# motherboard.net
KiCad netlist of a schematic drawn in EAGLE
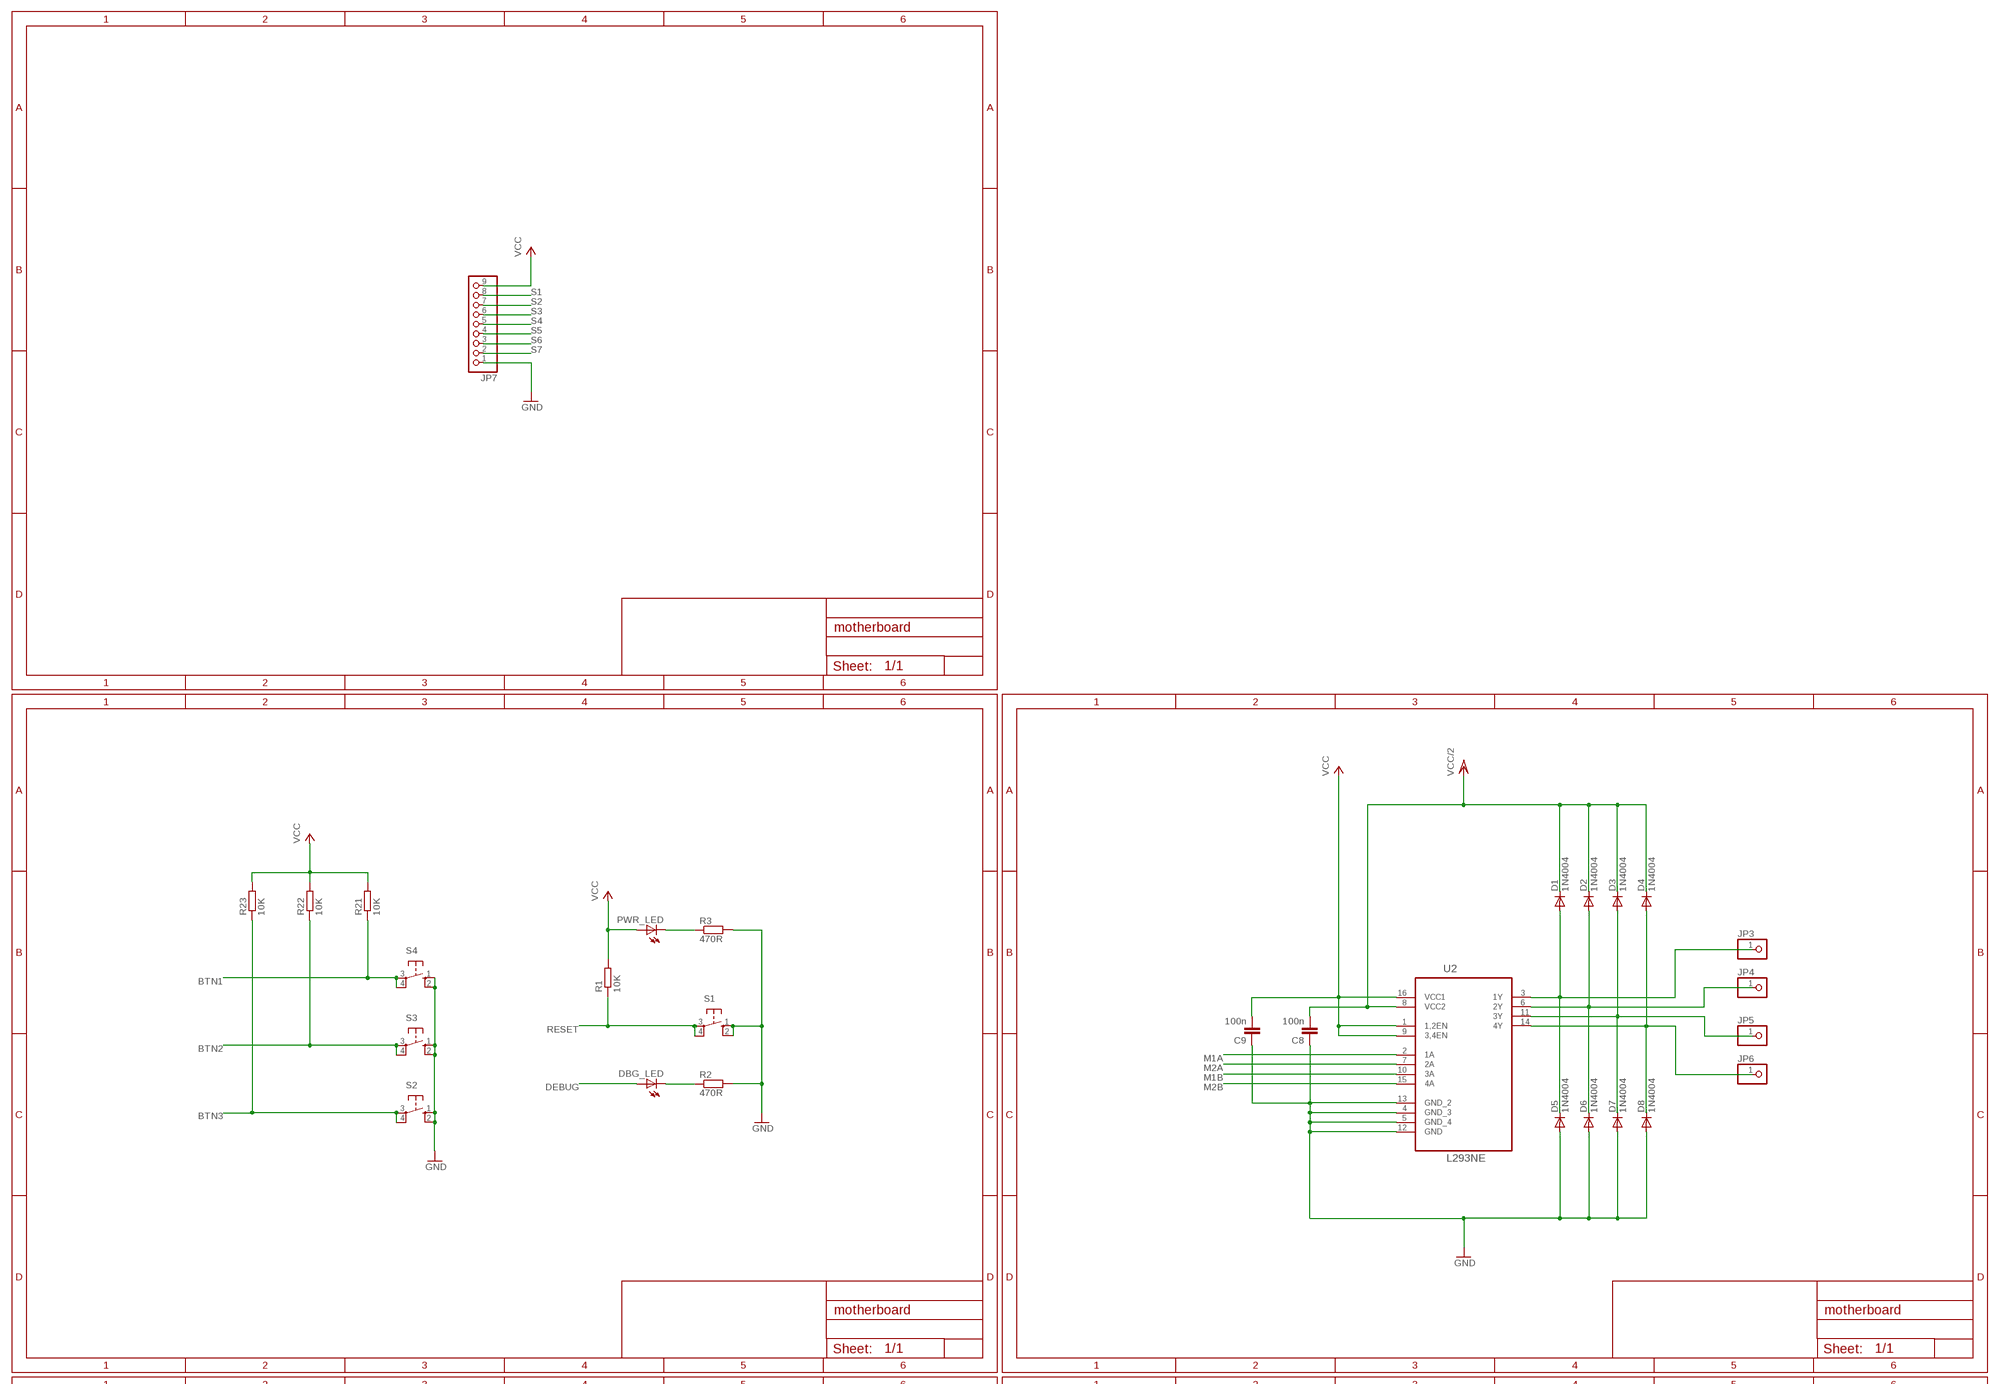
[diagram p0: schematic, sheet 1, part 1 of 2]
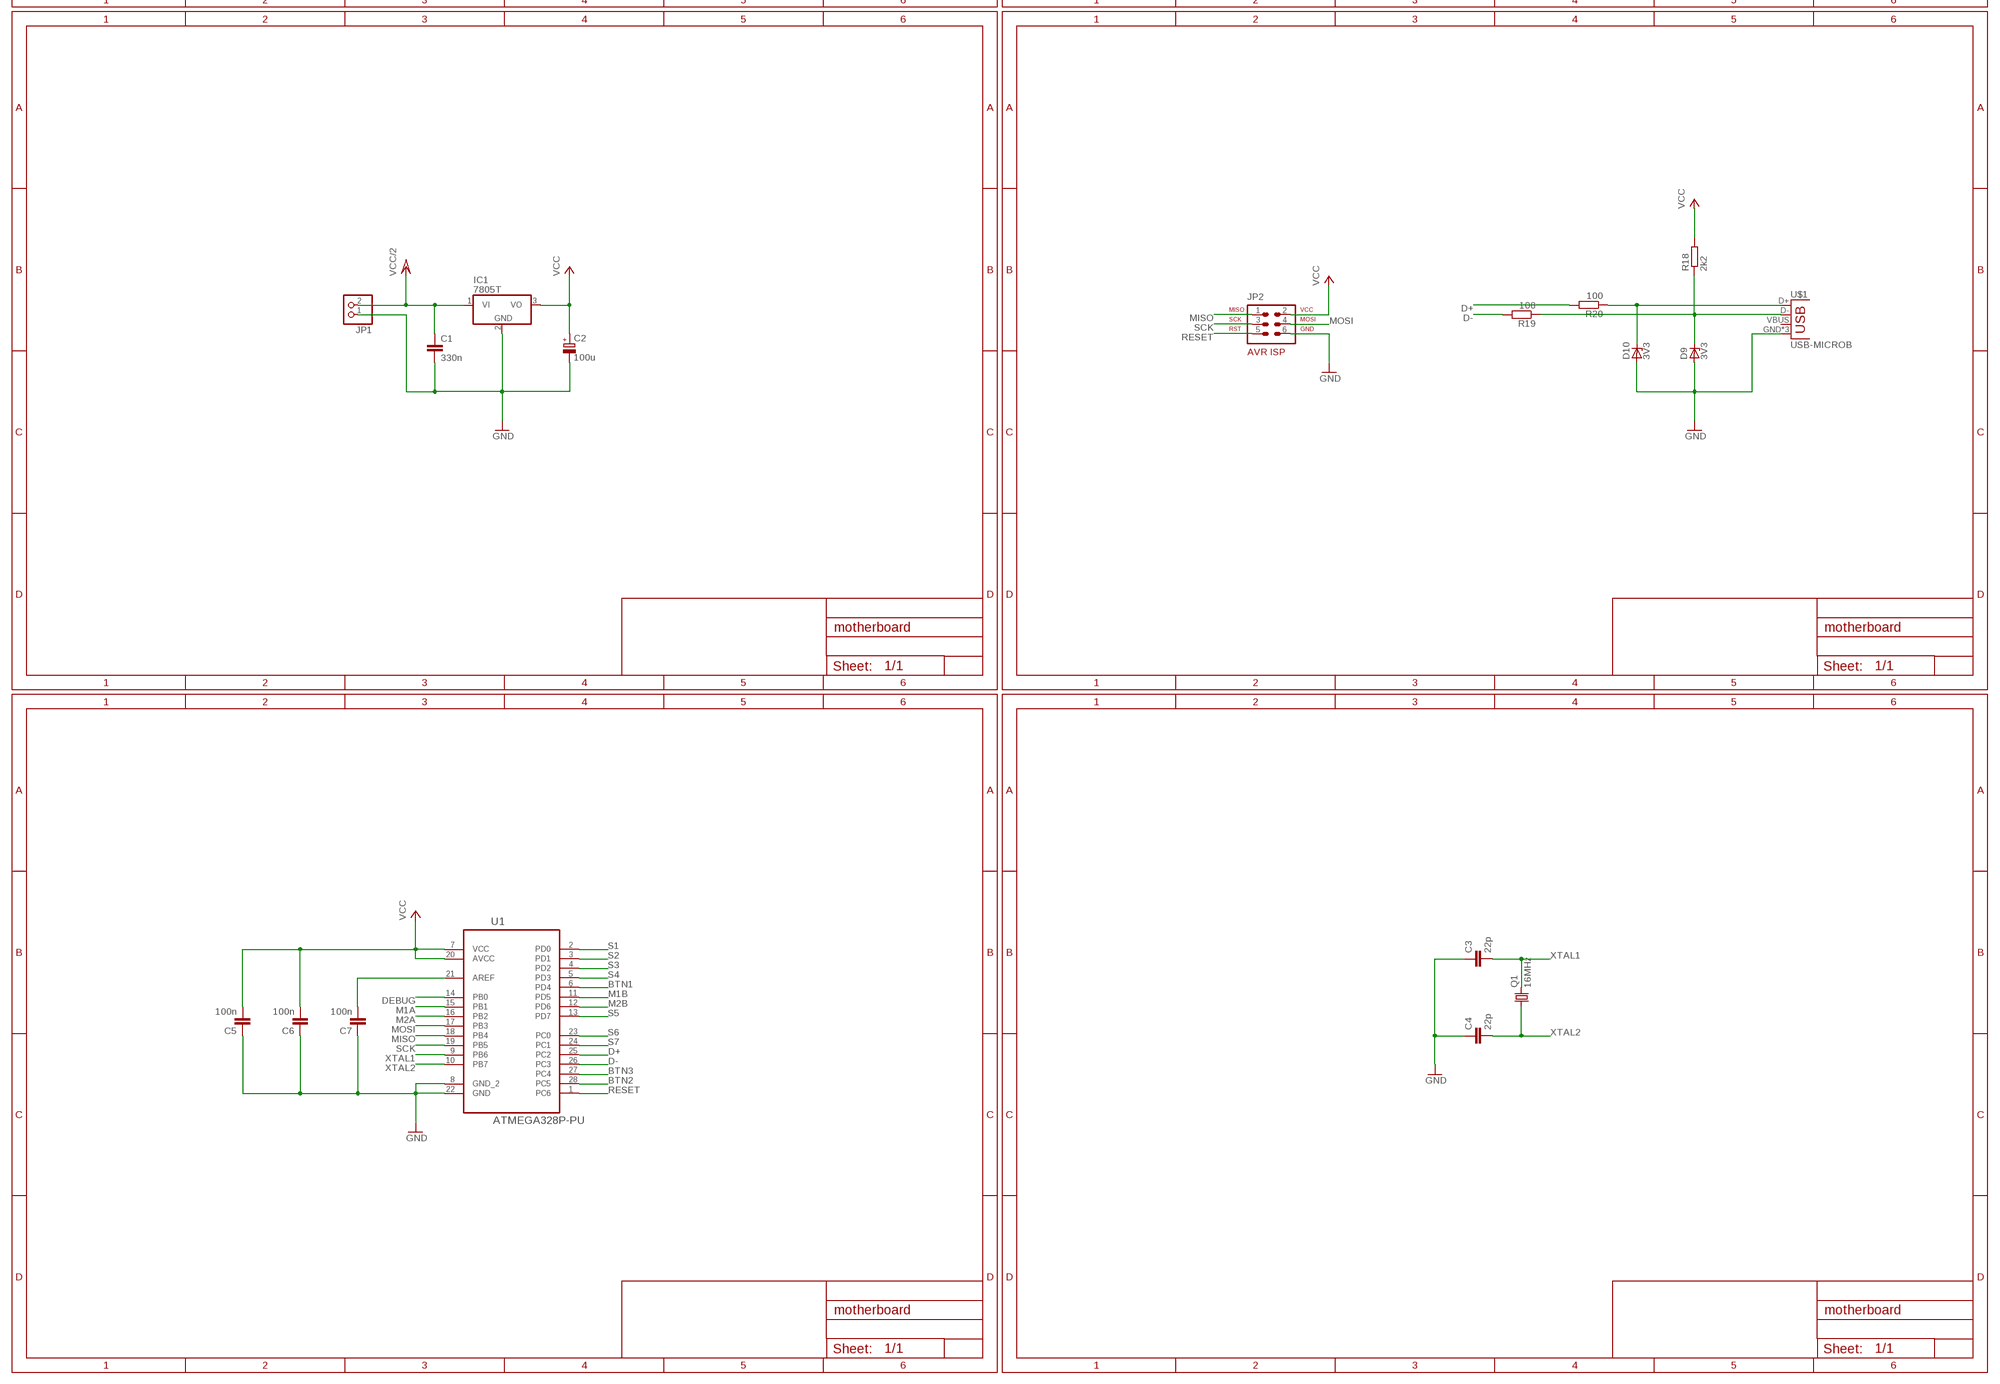
[diagram p1: schematic, sheet 1, part 2 of 2]

(export (version "E")
  (design (tool "Eeschema 10.0.6"))
  (components
    (comp (ref "C1")
      (value "330n")
      (footprint "eagle-import:C0805K")
      (libsource (lib "eagle-import") (part "C-EUC0805K"))
    )
    (comp (ref "C2")
      (value "100u")
      (footprint "eagle-import:E2,5-5")
      (libsource (lib "eagle-import") (part "CPOL-EUE2.5-5"))
    )
    (comp (ref "C3")
      (value "22p")
      (footprint "eagle-import:C0805K")
      (libsource (lib "eagle-import") (part "C-EUC0805K"))
    )
    (comp (ref "C4")
      (value "22p")
      (footprint "eagle-import:C0805K")
      (libsource (lib "eagle-import") (part "C-EUC0805K"))
    )
    (comp (ref "C5")
      (value "100n")
      (footprint "eagle-import:C0805K")
      (libsource (lib "eagle-import") (part "C-EUC0805K"))
    )
    (comp (ref "C6")
      (value "100n")
      (footprint "eagle-import:C0805K")
      (libsource (lib "eagle-import") (part "C-EUC0805K"))
    )
    (comp (ref "C7")
      (value "100n")
      (footprint "eagle-import:C0805K")
      (libsource (lib "eagle-import") (part "C-EUC0805K"))
    )
    (comp (ref "C8")
      (value "100n")
      (footprint "eagle-import:C0805K")
      (libsource (lib "eagle-import") (part "C-EUC0805K"))
    )
    (comp (ref "C9")
      (value "100n")
      (footprint "eagle-import:C0805K")
      (libsource (lib "eagle-import") (part "C-EUC0805K"))
    )
    (comp (ref "D1")
      (value "1N4004")
      (footprint "eagle-import:DO41-10")
      (libsource (lib "eagle-import") (part "1N4004"))
    )
    (comp (ref "D2")
      (value "1N4004")
      (footprint "eagle-import:DO41-10")
      (libsource (lib "eagle-import") (part "1N4004"))
    )
    (comp (ref "D3")
      (value "1N4004")
      (footprint "eagle-import:DO41-10")
      (libsource (lib "eagle-import") (part "1N4004"))
    )
    (comp (ref "D4")
      (value "1N4004")
      (footprint "eagle-import:DO41-10")
      (libsource (lib "eagle-import") (part "1N4004"))
    )
    (comp (ref "D5")
      (value "1N4004")
      (footprint "eagle-import:DO41-10")
      (libsource (lib "eagle-import") (part "1N4004"))
    )
    (comp (ref "D6")
      (value "1N4004")
      (footprint "eagle-import:DO41-10")
      (libsource (lib "eagle-import") (part "1N4004"))
    )
    (comp (ref "D7")
      (value "1N4004")
      (footprint "eagle-import:DO41-10")
      (libsource (lib "eagle-import") (part "1N4004"))
    )
    (comp (ref "D8")
      (value "1N4004")
      (footprint "eagle-import:DO41-10")
      (libsource (lib "eagle-import") (part "1N4004"))
    )
    (comp (ref "D9")
      (value "3V3")
      (footprint "eagle-import:DO41Z10")
      (libsource (lib "eagle-import") (part "ZENER-DIODEDO41Z10"))
    )
    (comp (ref "D10")
      (value "3V3")
      (footprint "eagle-import:DO41Z10")
      (libsource (lib "eagle-import") (part "ZENER-DIODEDO41Z10"))
    )
    (comp (ref "DBG_LED")
      (value "LED5MM")
      (footprint "eagle-import:LED5MM")
      (libsource (lib "eagle-import") (part "LED5MM"))
    )
    (comp (ref "IC1")
      (value "7805T")
      (footprint "eagle-import:TO220H")
      (libsource (lib "eagle-import") (part "78T05"))
    )
    (comp (ref "JP1")
      (value "PINHD-1X2")
      (footprint "eagle-import:1X02")
      (libsource (lib "eagle-import") (part "PINHD-1X2"))
    )
    (comp (ref "JP2")
      (value "AVR-ISP-6VERT")
      (footprint "eagle-import:AVR-ISP-6")
      (libsource (lib "eagle-import") (part "AVR-ISP-6VERT"))
    )
    (comp (ref "JP3")
      (value "PINHD-1X1")
      (footprint "eagle-import:1X01")
      (libsource (lib "eagle-import") (part "PINHD-1X1"))
    )
    (comp (ref "JP4")
      (value "PINHD-1X1")
      (footprint "eagle-import:1X01")
      (libsource (lib "eagle-import") (part "PINHD-1X1"))
    )
    (comp (ref "JP5")
      (value "PINHD-1X1")
      (footprint "eagle-import:1X01")
      (libsource (lib "eagle-import") (part "PINHD-1X1"))
    )
    (comp (ref "JP6")
      (value "PINHD-1X1")
      (footprint "eagle-import:1X01")
      (libsource (lib "eagle-import") (part "PINHD-1X1"))
    )
    (comp (ref "JP7")
      (value "PINHD-1X9")
      (footprint "eagle-import:1X09")
      (libsource (lib "eagle-import") (part "PINHD-1X9"))
    )
    (comp (ref "PWR_LED")
      (value "LED5MM")
      (footprint "eagle-import:LED5MM")
      (libsource (lib "eagle-import") (part "LED5MM"))
    )
    (comp (ref "Q1")
      (value "16MHz")
      (footprint "eagle-import:HC49_S")
      (libsource (lib "eagle-import") (part "CRYSTALHC49S"))
    )
    (comp (ref "R1")
      (value "10K")
      (footprint "eagle-import:M0805")
      (libsource (lib "eagle-import") (part "R-EU_M0805"))
    )
    (comp (ref "R2")
      (value "470R")
      (footprint "eagle-import:M0805")
      (libsource (lib "eagle-import") (part "R-EU_M0805"))
    )
    (comp (ref "R3")
      (value "470R")
      (footprint "eagle-import:M0805")
      (libsource (lib "eagle-import") (part "R-EU_M0805"))
    )
    (comp (ref "R18")
      (value "2k2")
      (footprint "eagle-import:M0805")
      (libsource (lib "eagle-import") (part "R-EU_M0805"))
    )
    (comp (ref "R19")
      (value "100")
      (footprint "eagle-import:M0805")
      (libsource (lib "eagle-import") (part "R-EU_M0805"))
    )
    (comp (ref "R20")
      (value "100")
      (footprint "eagle-import:M0805")
      (libsource (lib "eagle-import") (part "R-EU_M0805"))
    )
    (comp (ref "R21")
      (value "10K")
      (footprint "eagle-import:M0805")
      (libsource (lib "eagle-import") (part "R-EU_M0805"))
    )
    (comp (ref "R22")
      (value "10K")
      (footprint "eagle-import:M0805")
      (libsource (lib "eagle-import") (part "R-EU_M0805"))
    )
    (comp (ref "R23")
      (value "10K")
      (footprint "eagle-import:M0805")
      (libsource (lib "eagle-import") (part "R-EU_M0805"))
    )
    (comp (ref "S1")
      (value "10-XX")
      (footprint "eagle-import:B3F-10XX")
      (fields (field (name "MPN") "B3F-1000"))
      (libsource (lib "eagle-import") (part "10-XX"))
    )
    (comp (ref "S2")
      (value "10-XX")
      (footprint "eagle-import:B3F-10XX")
      (fields (field (name "MPN") "B3F-1000"))
      (libsource (lib "eagle-import") (part "10-XX"))
    )
    (comp (ref "S3")
      (value "10-XX")
      (footprint "eagle-import:B3F-10XX")
      (fields (field (name "MPN") "B3F-1000"))
      (libsource (lib "eagle-import") (part "10-XX"))
    )
    (comp (ref "S4")
      (value "10-XX")
      (footprint "eagle-import:B3F-10XX")
      (fields (field (name "MPN") "B3F-1000"))
      (libsource (lib "eagle-import") (part "10-XX"))
    )
    (comp (ref "U$1")
      (value "USB-MICROB")
      (footprint "eagle-import:USB-MICROB")
      (libsource (lib "eagle-import") (part "USB-MICROB"))
    )
    (comp (ref "U1")
      (value "ATMEGA328P-PU")
      (footprint "eagle-import:DIP254P762X457-28")
      (libsource (lib "eagle-import") (part "ATMEGA328P-PU"))
    )
    (comp (ref "U2")
      (value "L293NE")
      (footprint "eagle-import:DIP254P762X508-16")
      (libsource (lib "eagle-import") (part "L293NE"))
    )
  )
  (nets
    (net (code "1") (name "/BTN1") (class "Default")
      (node (ref "R21") (pin "1") (pinfunction "1_1") (pintype "passive"))
      (node (ref "S4") (pin "3") (pinfunction "P_3") (pintype "passive"))
      (node (ref "S4") (pin "4") (pinfunction "P1_4") (pintype "passive"))
      (node (ref "U1") (pin "6") (pinfunction "PD4_6") (pintype "bidirectional"))
    )
    (net (code "2") (name "/BTN2") (class "Default")
      (node (ref "R22") (pin "1") (pinfunction "1_1") (pintype "passive"))
      (node (ref "S3") (pin "3") (pinfunction "P_3") (pintype "passive"))
      (node (ref "S3") (pin "4") (pinfunction "P1_4") (pintype "passive"))
      (node (ref "U1") (pin "28") (pinfunction "PC5_28") (pintype "bidirectional"))
    )
    (net (code "3") (name "/BTN3") (class "Default")
      (node (ref "R23") (pin "1") (pinfunction "1_1") (pintype "passive"))
      (node (ref "S2") (pin "3") (pinfunction "P_3") (pintype "passive"))
      (node (ref "S2") (pin "4") (pinfunction "P1_4") (pintype "passive"))
      (node (ref "U1") (pin "27") (pinfunction "PC4_27") (pintype "bidirectional"))
    )
    (net (code "4") (name "/D+") (class "Default")
      (node (ref "R20") (pin "2") (pinfunction "2_2") (pintype "passive"))
      (node (ref "U1") (pin "25") (pinfunction "PC2_25") (pintype "bidirectional"))
    )
    (net (code "5") (name "/D-") (class "Default")
      (node (ref "R19") (pin "2") (pinfunction "2_2") (pintype "passive"))
      (node (ref "U1") (pin "26") (pinfunction "PC3_26") (pintype "bidirectional"))
    )
    (net (code "6") (name "/DEBUG") (class "Default")
      (node (ref "DBG_LED") (pin "A") (pinfunction "A_A") (pintype "passive"))
      (node (ref "U1") (pin "14") (pinfunction "PB0_14") (pintype "bidirectional"))
    )
    (net (code "7") (name "/M1A") (class "Default")
      (node (ref "U1") (pin "15") (pinfunction "PB1_15") (pintype "bidirectional"))
      (node (ref "U2") (pin "2") (pinfunction "1A_2") (pintype "input"))
    )
    (net (code "8") (name "/M1B") (class "Default")
      (node (ref "U1") (pin "11") (pinfunction "PD5_11") (pintype "bidirectional"))
      (node (ref "U2") (pin "10") (pinfunction "3A_10") (pintype "input"))
    )
    (net (code "9") (name "/M2A") (class "Default")
      (node (ref "U1") (pin "16") (pinfunction "PB2_16") (pintype "bidirectional"))
      (node (ref "U2") (pin "7") (pinfunction "2A_7") (pintype "input"))
    )
    (net (code "10") (name "/M2B") (class "Default")
      (node (ref "U1") (pin "12") (pinfunction "PD6_12") (pintype "bidirectional"))
      (node (ref "U2") (pin "15") (pinfunction "4A_15") (pintype "input"))
    )
    (net (code "11") (name "/MISO") (class "Default")
      (node (ref "JP2") (pin "1") (pinfunction "1_1") (pintype "passive"))
      (node (ref "U1") (pin "18") (pinfunction "PB4_18") (pintype "bidirectional"))
    )
    (net (code "12") (name "/MOSI") (class "Default")
      (node (ref "JP2") (pin "4") (pinfunction "4_4") (pintype "passive"))
      (node (ref "U1") (pin "17") (pinfunction "PB3_17") (pintype "bidirectional"))
    )
    (net (code "13") (name "/RESET") (class "Default")
      (node (ref "JP2") (pin "5") (pinfunction "5_5") (pintype "passive"))
      (node (ref "R1") (pin "1") (pinfunction "1_1") (pintype "passive"))
      (node (ref "S1") (pin "3") (pinfunction "P_3") (pintype "passive"))
      (node (ref "S1") (pin "4") (pinfunction "P1_4") (pintype "passive"))
      (node (ref "U1") (pin "1") (pinfunction "PC6_1") (pintype "bidirectional"))
    )
    (net (code "14") (name "/S1") (class "Default")
      (node (ref "JP7") (pin "8") (pinfunction "8_8") (pintype "passive"))
      (node (ref "U1") (pin "2") (pinfunction "PD0_2") (pintype "bidirectional"))
    )
    (net (code "15") (name "/S2") (class "Default")
      (node (ref "JP7") (pin "7") (pinfunction "7_7") (pintype "passive"))
      (node (ref "U1") (pin "3") (pinfunction "PD1_3") (pintype "bidirectional"))
    )
    (net (code "16") (name "/S3") (class "Default")
      (node (ref "JP7") (pin "6") (pinfunction "6_6") (pintype "passive"))
      (node (ref "U1") (pin "4") (pinfunction "PD2_4") (pintype "bidirectional"))
    )
    (net (code "17") (name "/S4") (class "Default")
      (node (ref "JP7") (pin "5") (pinfunction "5_5") (pintype "passive"))
      (node (ref "U1") (pin "5") (pinfunction "PD3_5") (pintype "bidirectional"))
    )
    (net (code "18") (name "/S5") (class "Default")
      (node (ref "JP7") (pin "4") (pinfunction "4_4") (pintype "passive"))
      (node (ref "U1") (pin "13") (pinfunction "PD7_13") (pintype "bidirectional"))
    )
    (net (code "19") (name "/S6") (class "Default")
      (node (ref "JP7") (pin "3") (pinfunction "3_3") (pintype "passive"))
      (node (ref "U1") (pin "23") (pinfunction "PC0_23") (pintype "bidirectional"))
    )
    (net (code "20") (name "/S7") (class "Default")
      (node (ref "JP7") (pin "2") (pinfunction "2_2") (pintype "passive"))
      (node (ref "U1") (pin "24") (pinfunction "PC1_24") (pintype "bidirectional"))
    )
    (net (code "21") (name "/SCK") (class "Default")
      (node (ref "JP2") (pin "3") (pinfunction "3_3") (pintype "passive"))
      (node (ref "U1") (pin "19") (pinfunction "PB5_19") (pintype "bidirectional"))
    )
    (net (code "22") (name "/XTAL1") (class "Default")
      (node (ref "C3") (pin "2") (pinfunction "2_2") (pintype "passive"))
      (node (ref "Q1") (pin "2") (pinfunction "2_2") (pintype "passive"))
      (node (ref "U1") (pin "9") (pinfunction "PB6_9") (pintype "bidirectional"))
    )
    (net (code "23") (name "/XTAL2") (class "Default")
      (node (ref "C4") (pin "2") (pinfunction "2_2") (pintype "passive"))
      (node (ref "Q1") (pin "1") (pinfunction "1_1") (pintype "passive"))
      (node (ref "U1") (pin "10") (pinfunction "PB7_10") (pintype "bidirectional"))
    )
    (net (code "24") (name "GND") (class "Default")
      (node (ref "C1") (pin "2") (pinfunction "2_2") (pintype "passive"))
      (node (ref "C2") (pin "-") (pinfunction "-_-") (pintype "passive"))
      (node (ref "C3") (pin "1") (pinfunction "1_1") (pintype "passive"))
      (node (ref "C4") (pin "1") (pinfunction "1_1") (pintype "passive"))
      (node (ref "C5") (pin "1") (pinfunction "1_1") (pintype "passive"))
      (node (ref "C6") (pin "1") (pinfunction "1_1") (pintype "passive"))
      (node (ref "C7") (pin "1") (pinfunction "1_1") (pintype "passive"))
      (node (ref "C8") (pin "1") (pinfunction "1_1") (pintype "passive"))
      (node (ref "C9") (pin "1") (pinfunction "1_1") (pintype "passive"))
      (node (ref "D10") (pin "A") (pinfunction "A_A") (pintype "passive"))
      (node (ref "D5") (pin "A") (pinfunction "A_A") (pintype "passive"))
      (node (ref "D6") (pin "A") (pinfunction "A_A") (pintype "passive"))
      (node (ref "D7") (pin "A") (pinfunction "A_A") (pintype "passive"))
      (node (ref "D8") (pin "A") (pinfunction "A_A") (pintype "passive"))
      (node (ref "D9") (pin "A") (pinfunction "A_A") (pintype "passive"))
      (node (ref "IC1") (pin "2") (pinfunction "GND_2") (pintype "passive"))
      (node (ref "JP1") (pin "1") (pinfunction "1_1") (pintype "passive"))
      (node (ref "JP2") (pin "6") (pinfunction "6_6") (pintype "passive"))
      (node (ref "JP7") (pin "1") (pinfunction "1_1") (pintype "passive"))
      (node (ref "R2") (pin "2") (pinfunction "2_2") (pintype "passive"))
      (node (ref "R3") (pin "2") (pinfunction "2_2") (pintype "passive"))
      (node (ref "S1") (pin "1") (pinfunction "S_1") (pintype "passive"))
      (node (ref "S1") (pin "2") (pinfunction "S1_2") (pintype "passive"))
      (node (ref "S2") (pin "1") (pinfunction "S_1") (pintype "passive"))
      (node (ref "S2") (pin "2") (pinfunction "S1_2") (pintype "passive"))
      (node (ref "S3") (pin "1") (pinfunction "S_1") (pintype "passive"))
      (node (ref "S3") (pin "2") (pinfunction "S1_2") (pintype "passive"))
      (node (ref "S4") (pin "1") (pinfunction "S_1") (pintype "passive"))
      (node (ref "S4") (pin "2") (pinfunction "S1_2") (pintype "passive"))
      (node (ref "U$1") (pin "GND") (pinfunction "GND_GND") (pintype "bidirectional"))
      (node (ref "U$1") (pin "MT1") (pinfunction "GND_MT1") (pintype "bidirectional"))
      (node (ref "U$1") (pin "MT2") (pinfunction "GND_MT2") (pintype "bidirectional"))
      (node (ref "U1") (pin "22") (pinfunction "GND_22") (pintype "passive"))
      (node (ref "U1") (pin "8") (pinfunction "GND_2_8") (pintype "passive"))
      (node (ref "U2") (pin "12") (pinfunction "GND_12") (pintype "passive"))
      (node (ref "U2") (pin "13") (pinfunction "GND_2_13") (pintype "passive"))
      (node (ref "U2") (pin "4") (pinfunction "GND_3_4") (pintype "passive"))
      (node (ref "U2") (pin "5") (pinfunction "GND_4_5") (pintype "passive"))
    )
    (net (code "25") (name "Net-(D9-PadC)") (class "Default")
      (node (ref "D9") (pin "C") (pinfunction "C_C") (pintype "passive"))
      (node (ref "R18") (pin "1") (pinfunction "1_1") (pintype "passive"))
      (node (ref "R19") (pin "1") (pinfunction "1_1") (pintype "passive"))
      (node (ref "U$1") (pin "D-") (pinfunction "D-_D-") (pintype "bidirectional"))
    )
    (net (code "26") (name "Net-(D10-PadC)") (class "Default")
      (node (ref "D10") (pin "C") (pinfunction "C_C") (pintype "passive"))
      (node (ref "R20") (pin "1") (pinfunction "1_1") (pintype "passive"))
      (node (ref "U$1") (pin "D+") (pinfunction "D+_D+") (pintype "bidirectional"))
    )
    (net (code "27") (name "Net-(DBG_LED-C)") (class "Default")
      (node (ref "DBG_LED") (pin "K") (pinfunction "C_K") (pintype "passive"))
      (node (ref "R2") (pin "1") (pinfunction "1_1") (pintype "passive"))
    )
    (net (code "28") (name "Net-(PWR_LED-C)") (class "Default")
      (node (ref "PWR_LED") (pin "K") (pinfunction "C_K") (pintype "passive"))
      (node (ref "R3") (pin "1") (pinfunction "1_1") (pintype "passive"))
    )
    (net (code "29") (name "Net-(U1-AREF)") (class "Default")
      (node (ref "C7") (pin "2") (pinfunction "2_2") (pintype "passive"))
      (node (ref "U1") (pin "21") (pinfunction "AREF_21") (pintype "input"))
    )
    (net (code "30") (name "Net-(U2-1Y)") (class "Default")
      (node (ref "D1") (pin "A") (pinfunction "A_A") (pintype "passive"))
      (node (ref "D5") (pin "C") (pinfunction "C_C") (pintype "passive"))
      (node (ref "JP3") (pin "1") (pinfunction "1_1") (pintype "passive"))
      (node (ref "U2") (pin "3") (pinfunction "1Y_3") (pintype "output"))
    )
    (net (code "31") (name "Net-(U2-2Y)") (class "Default")
      (node (ref "D2") (pin "A") (pinfunction "A_A") (pintype "passive"))
      (node (ref "D6") (pin "C") (pinfunction "C_C") (pintype "passive"))
      (node (ref "JP4") (pin "1") (pinfunction "1_1") (pintype "passive"))
      (node (ref "U2") (pin "6") (pinfunction "2Y_6") (pintype "output"))
    )
    (net (code "32") (name "Net-(U2-3Y)") (class "Default")
      (node (ref "D3") (pin "A") (pinfunction "A_A") (pintype "passive"))
      (node (ref "D7") (pin "C") (pinfunction "C_C") (pintype "passive"))
      (node (ref "JP5") (pin "1") (pinfunction "1_1") (pintype "passive"))
      (node (ref "U2") (pin "11") (pinfunction "3Y_11") (pintype "output"))
    )
    (net (code "33") (name "Net-(U2-4Y)") (class "Default")
      (node (ref "D4") (pin "A") (pinfunction "A_A") (pintype "passive"))
      (node (ref "D8") (pin "C") (pinfunction "C_C") (pintype "passive"))
      (node (ref "JP6") (pin "1") (pinfunction "1_1") (pintype "passive"))
      (node (ref "U2") (pin "14") (pinfunction "4Y_14") (pintype "output"))
    )
    (net (code "34") (name "VCC") (class "Default")
      (node (ref "C2") (pin "+") (pinfunction "+_+") (pintype "passive"))
      (node (ref "C5") (pin "2") (pinfunction "2_2") (pintype "passive"))
      (node (ref "C6") (pin "2") (pinfunction "2_2") (pintype "passive"))
      (node (ref "C9") (pin "2") (pinfunction "2_2") (pintype "passive"))
      (node (ref "IC1") (pin "3") (pinfunction "VO_3") (pintype "passive"))
      (node (ref "JP2") (pin "2") (pinfunction "2_2") (pintype "passive"))
      (node (ref "JP7") (pin "9") (pinfunction "9_9") (pintype "passive"))
      (node (ref "PWR_LED") (pin "A") (pinfunction "A_A") (pintype "passive"))
      (node (ref "R1") (pin "2") (pinfunction "2_2") (pintype "passive"))
      (node (ref "R18") (pin "2") (pinfunction "2_2") (pintype "passive"))
      (node (ref "R21") (pin "2") (pinfunction "2_2") (pintype "passive"))
      (node (ref "R22") (pin "2") (pinfunction "2_2") (pintype "passive"))
      (node (ref "R23") (pin "2") (pinfunction "2_2") (pintype "passive"))
      (node (ref "U1") (pin "20") (pinfunction "AVCC_20") (pintype "power_in"))
      (node (ref "U1") (pin "7") (pinfunction "VCC_7") (pintype "power_in"))
      (node (ref "U2") (pin "1") (pinfunction "1,2EN_1") (pintype "input"))
      (node (ref "U2") (pin "16") (pinfunction "VCC1_16") (pintype "power_in"))
      (node (ref "U2") (pin "9") (pinfunction "3,4EN_9") (pintype "input"))
    )
    (net (code "35") (name "VCC{slash}2") (class "Default")
      (node (ref "C1") (pin "1") (pinfunction "1_1") (pintype "passive"))
      (node (ref "C8") (pin "2") (pinfunction "2_2") (pintype "passive"))
      (node (ref "D1") (pin "C") (pinfunction "C_C") (pintype "passive"))
      (node (ref "D2") (pin "C") (pinfunction "C_C") (pintype "passive"))
      (node (ref "D3") (pin "C") (pinfunction "C_C") (pintype "passive"))
      (node (ref "D4") (pin "C") (pinfunction "C_C") (pintype "passive"))
      (node (ref "IC1") (pin "1") (pinfunction "VI_1") (pintype "input"))
      (node (ref "JP1") (pin "2") (pinfunction "2_2") (pintype "passive"))
      (node (ref "U2") (pin "8") (pinfunction "VCC2_8") (pintype "power_in"))
    )
    (net (code "36") (name "unconnected-(U$1-PadVBUS)") (class "Default")
      (node (ref "U$1") (pin "VBUS") (pinfunction "VBUS_VBUS") (pintype "bidirectional"))
    )
  )
)
